# swigert.net
KiCad netlist of a schematic drawn in EAGLE
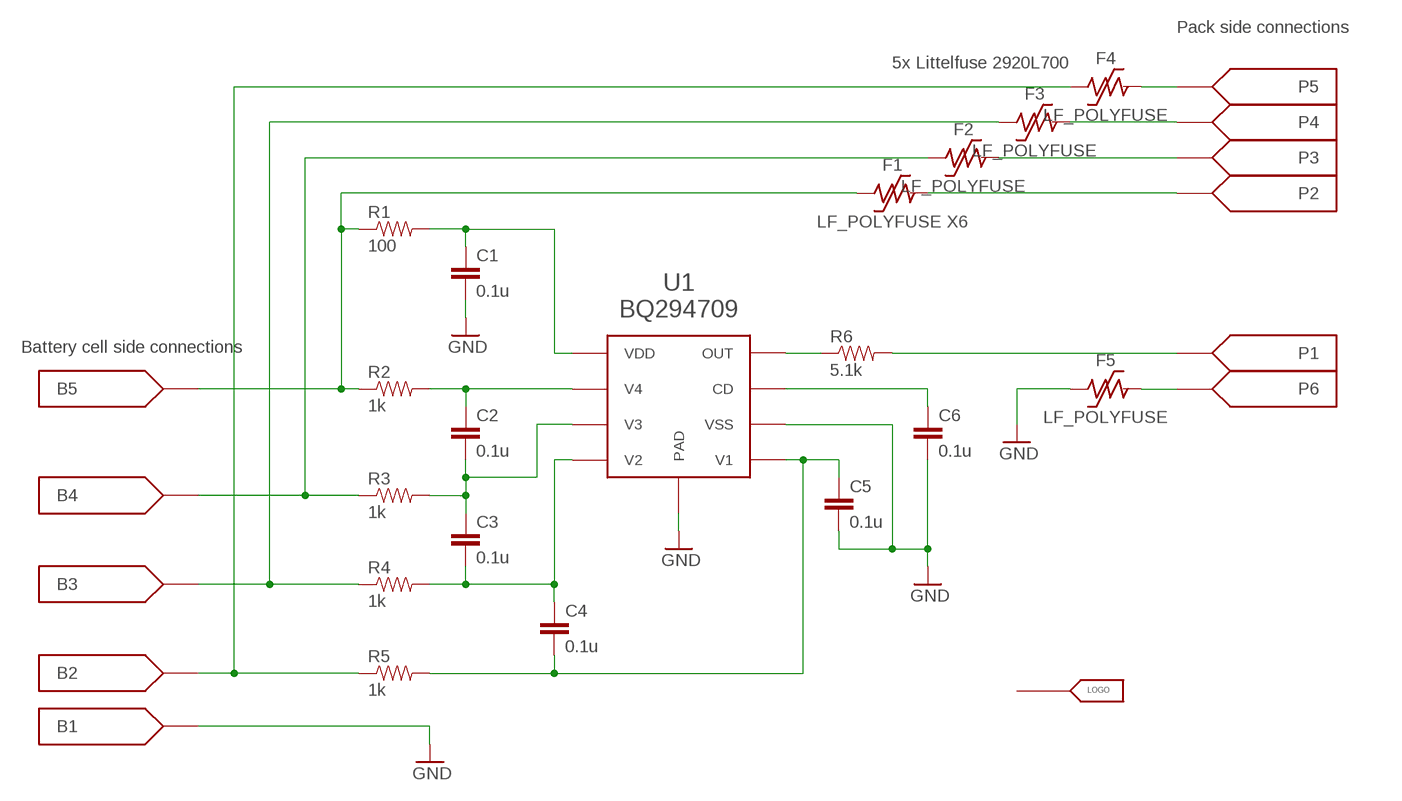
[diagram p0: schematic, sheet 1]

(export (version "E")
  (design (tool "Eeschema 10.0.6"))
  (components
    (comp (ref "B1")
      (value "MOLEX_SRT")
      (footprint "eagle-import:MOLEX_SRT_14-20")
      (libsource (lib "eagle-import") (part "MOLEX_SRT"))
    )
    (comp (ref "B2")
      (value "MOLEX_SRT")
      (footprint "eagle-import:MOLEX_SRT_14-20")
      (libsource (lib "eagle-import") (part "MOLEX_SRT"))
    )
    (comp (ref "B3")
      (value "MOLEX_SRT")
      (footprint "eagle-import:MOLEX_SRT_14-20")
      (libsource (lib "eagle-import") (part "MOLEX_SRT"))
    )
    (comp (ref "B4")
      (value "MOLEX_SRT")
      (footprint "eagle-import:MOLEX_SRT_14-20")
      (libsource (lib "eagle-import") (part "MOLEX_SRT"))
    )
    (comp (ref "B5")
      (value "MOLEX_SRT")
      (footprint "eagle-import:MOLEX_SRT_14-20")
      (libsource (lib "eagle-import") (part "MOLEX_SRT"))
    )
    (comp (ref "C1")
      (value "0.1u")
      (footprint "eagle-import:1206")
      (libsource (lib "eagle-import") (part "CAP1206"))
    )
    (comp (ref "C2")
      (value "0.1u")
      (footprint "eagle-import:1206")
      (libsource (lib "eagle-import") (part "CAP1206"))
    )
    (comp (ref "C3")
      (value "0.1u")
      (footprint "eagle-import:1206")
      (libsource (lib "eagle-import") (part "CAP1206"))
    )
    (comp (ref "C4")
      (value "0.1u")
      (footprint "eagle-import:1206")
      (libsource (lib "eagle-import") (part "CAP1206"))
    )
    (comp (ref "C5")
      (value "0.1u")
      (footprint "eagle-import:1206")
      (libsource (lib "eagle-import") (part "CAP1206"))
    )
    (comp (ref "C6")
      (value "0.1u")
      (footprint "eagle-import:1206")
      (libsource (lib "eagle-import") (part "CAP1206"))
    )
    (comp (ref "F1")
      (value "LF_POLYFUSE X6")
      (footprint "eagle-import:2920")
      (libsource (lib "eagle-import") (part "LF_POLYFUSE"))
    )
    (comp (ref "F2")
      (value "LF_POLYFUSE")
      (footprint "eagle-import:2920")
      (libsource (lib "eagle-import") (part "LF_POLYFUSE"))
    )
    (comp (ref "F3")
      (value "LF_POLYFUSE")
      (footprint "eagle-import:2920")
      (libsource (lib "eagle-import") (part "LF_POLYFUSE"))
    )
    (comp (ref "F4")
      (value "LF_POLYFUSE")
      (footprint "eagle-import:2920")
      (libsource (lib "eagle-import") (part "LF_POLYFUSE"))
    )
    (comp (ref "F5")
      (value "LF_POLYFUSE")
      (footprint "eagle-import:2920")
      (libsource (lib "eagle-import") (part "LF_POLYFUSE"))
    )
    (comp (ref "LOGO")
      (value "SU_LOGO-DUMMY2")
      (footprint "eagle-import:SU_LOGO_SS")
      (libsource (lib "eagle-import") (part "SU_LOGO-DUMMY2"))
    )
    (comp (ref "P1")
      (value "MOLEX_SRT")
      (footprint "eagle-import:MOLEX_SRT_14-20")
      (libsource (lib "eagle-import") (part "MOLEX_SRT"))
    )
    (comp (ref "P2")
      (value "MOLEX_SRT")
      (footprint "eagle-import:MOLEX_SRT_14-20")
      (libsource (lib "eagle-import") (part "MOLEX_SRT"))
    )
    (comp (ref "P3")
      (value "MOLEX_SRT")
      (footprint "eagle-import:MOLEX_SRT_14-20")
      (libsource (lib "eagle-import") (part "MOLEX_SRT"))
    )
    (comp (ref "P4")
      (value "MOLEX_SRT")
      (footprint "eagle-import:MOLEX_SRT_14-20")
      (libsource (lib "eagle-import") (part "MOLEX_SRT"))
    )
    (comp (ref "P5")
      (value "MOLEX_SRT")
      (footprint "eagle-import:MOLEX_SRT_14-20")
      (libsource (lib "eagle-import") (part "MOLEX_SRT"))
    )
    (comp (ref "P6")
      (value "MOLEX_SRT")
      (footprint "eagle-import:MOLEX_SRT_14-20")
      (libsource (lib "eagle-import") (part "MOLEX_SRT"))
    )
    (comp (ref "R1")
      (value "100")
      (footprint "eagle-import:1206")
      (libsource (lib "eagle-import") (part "RESISTOR1206"))
    )
    (comp (ref "R2")
      (value "1k")
      (footprint "eagle-import:1206")
      (libsource (lib "eagle-import") (part "RESISTOR1206"))
    )
    (comp (ref "R3")
      (value "1k")
      (footprint "eagle-import:1206")
      (libsource (lib "eagle-import") (part "RESISTOR1206"))
    )
    (comp (ref "R4")
      (value "1k")
      (footprint "eagle-import:1206")
      (libsource (lib "eagle-import") (part "RESISTOR1206"))
    )
    (comp (ref "R5")
      (value "1k")
      (footprint "eagle-import:1206")
      (libsource (lib "eagle-import") (part "RESISTOR1206"))
    )
    (comp (ref "R6")
      (value "5.1k")
      (footprint "eagle-import:1206")
      (libsource (lib "eagle-import") (part "RESISTOR1206"))
    )
    (comp (ref "U1")
      (value "BQ294709")
      (footprint "eagle-import:WSON8")
      (libsource (lib "eagle-import") (part "BQ2947"))
    )
  )
  (nets
    (net (code "1") (name "GND") (class "Default")
      (node (ref "B1") (pin "P$1") (pinfunction "P1_P$1") (pintype "bidirectional"))
      (node (ref "B1") (pin "P$2") (pinfunction "P1_P$2") (pintype "bidirectional"))
      (node (ref "C1") (pin "2") (pinfunction "2_2") (pintype "passive"))
      (node (ref "C5") (pin "2") (pinfunction "2_2") (pintype "passive"))
      (node (ref "C6") (pin "2") (pinfunction "2_2") (pintype "passive"))
      (node (ref "F5") (pin "P$1") (pinfunction "P$1_P$1") (pintype "bidirectional"))
      (node (ref "U1") (pin "P$6") (pinfunction "VSS_P$6") (pintype "bidirectional"))
      (node (ref "U1") (pin "P$9") (pinfunction "PAD_P$9") (pintype "bidirectional"))
      (node (ref "U1") (pin "P$9_1") (pinfunction "PAD_P$9_1") (pintype "bidirectional"))
      (node (ref "U1") (pin "P$9_2") (pinfunction "PAD_P$9_2") (pintype "bidirectional"))
    )
    (net (code "2") (name "Net-(B2-P1-PadP$1)") (class "Default")
      (node (ref "B2") (pin "P$1") (pinfunction "P1_P$1") (pintype "bidirectional"))
      (node (ref "B2") (pin "P$2") (pinfunction "P1_P$2") (pintype "bidirectional"))
      (node (ref "F4") (pin "P$1") (pinfunction "P$1_P$1") (pintype "bidirectional"))
      (node (ref "R5") (pin "1") (pinfunction "1_1") (pintype "passive"))
    )
    (net (code "3") (name "Net-(B3-P1-PadP$1)") (class "Default")
      (node (ref "B3") (pin "P$1") (pinfunction "P1_P$1") (pintype "bidirectional"))
      (node (ref "B3") (pin "P$2") (pinfunction "P1_P$2") (pintype "bidirectional"))
      (node (ref "F3") (pin "P$1") (pinfunction "P$1_P$1") (pintype "bidirectional"))
      (node (ref "R4") (pin "1") (pinfunction "1_1") (pintype "passive"))
    )
    (net (code "4") (name "Net-(B4-P1-PadP$1)") (class "Default")
      (node (ref "B4") (pin "P$1") (pinfunction "P1_P$1") (pintype "bidirectional"))
      (node (ref "B4") (pin "P$2") (pinfunction "P1_P$2") (pintype "bidirectional"))
      (node (ref "F2") (pin "P$1") (pinfunction "P$1_P$1") (pintype "bidirectional"))
      (node (ref "R3") (pin "1") (pinfunction "1_1") (pintype "passive"))
    )
    (net (code "5") (name "Net-(B5-P1-PadP$1)") (class "Default")
      (node (ref "B5") (pin "P$1") (pinfunction "P1_P$1") (pintype "bidirectional"))
      (node (ref "B5") (pin "P$2") (pinfunction "P1_P$2") (pintype "bidirectional"))
      (node (ref "F1") (pin "P$1") (pinfunction "P$1_P$1") (pintype "bidirectional"))
      (node (ref "R1") (pin "1") (pinfunction "1_1") (pintype "passive"))
      (node (ref "R2") (pin "1") (pinfunction "1_1") (pintype "passive"))
    )
    (net (code "6") (name "Net-(F1-PadP$2)") (class "Default")
      (node (ref "F1") (pin "P$2") (pinfunction "P$2_P$2") (pintype "bidirectional"))
      (node (ref "P2") (pin "P$1") (pinfunction "P1_P$1") (pintype "bidirectional"))
      (node (ref "P2") (pin "P$2") (pinfunction "P1_P$2") (pintype "bidirectional"))
    )
    (net (code "7") (name "Net-(F2-PadP$2)") (class "Default")
      (node (ref "F2") (pin "P$2") (pinfunction "P$2_P$2") (pintype "bidirectional"))
      (node (ref "P3") (pin "P$1") (pinfunction "P1_P$1") (pintype "bidirectional"))
      (node (ref "P3") (pin "P$2") (pinfunction "P1_P$2") (pintype "bidirectional"))
    )
    (net (code "8") (name "Net-(F3-PadP$2)") (class "Default")
      (node (ref "F3") (pin "P$2") (pinfunction "P$2_P$2") (pintype "bidirectional"))
      (node (ref "P4") (pin "P$1") (pinfunction "P1_P$1") (pintype "bidirectional"))
      (node (ref "P4") (pin "P$2") (pinfunction "P1_P$2") (pintype "bidirectional"))
    )
    (net (code "9") (name "Net-(F4-PadP$2)") (class "Default")
      (node (ref "F4") (pin "P$2") (pinfunction "P$2_P$2") (pintype "bidirectional"))
      (node (ref "P5") (pin "P$1") (pinfunction "P1_P$1") (pintype "bidirectional"))
      (node (ref "P5") (pin "P$2") (pinfunction "P1_P$2") (pintype "bidirectional"))
    )
    (net (code "10") (name "Net-(F5-PadP$2)") (class "Default")
      (node (ref "F5") (pin "P$2") (pinfunction "P$2_P$2") (pintype "bidirectional"))
      (node (ref "P6") (pin "P$1") (pinfunction "P1_P$1") (pintype "bidirectional"))
      (node (ref "P6") (pin "P$2") (pinfunction "P1_P$2") (pintype "bidirectional"))
    )
    (net (code "11") (name "Net-(P1-P1-PadP$1)") (class "Default")
      (node (ref "P1") (pin "P$1") (pinfunction "P1_P$1") (pintype "bidirectional"))
      (node (ref "P1") (pin "P$2") (pinfunction "P1_P$2") (pintype "bidirectional"))
      (node (ref "R6") (pin "2") (pinfunction "2_2") (pintype "passive"))
    )
    (net (code "12") (name "Net-(U1-CD)") (class "Default")
      (node (ref "C6") (pin "1") (pinfunction "1_1") (pintype "passive"))
      (node (ref "U1") (pin "P$7") (pinfunction "CD_P$7") (pintype "bidirectional"))
    )
    (net (code "13") (name "Net-(U1-OUT)") (class "Default")
      (node (ref "R6") (pin "1") (pinfunction "1_1") (pintype "passive"))
      (node (ref "U1") (pin "P$8") (pinfunction "OUT_P$8") (pintype "bidirectional"))
    )
    (net (code "14") (name "Net-(U1-V1)") (class "Default")
      (node (ref "C4") (pin "2") (pinfunction "2_2") (pintype "passive"))
      (node (ref "C5") (pin "1") (pinfunction "1_1") (pintype "passive"))
      (node (ref "R5") (pin "2") (pinfunction "2_2") (pintype "passive"))
      (node (ref "U1") (pin "P$5") (pinfunction "V1_P$5") (pintype "bidirectional"))
    )
    (net (code "15") (name "Net-(U1-V2)") (class "Default")
      (node (ref "C3") (pin "2") (pinfunction "2_2") (pintype "passive"))
      (node (ref "C4") (pin "1") (pinfunction "1_1") (pintype "passive"))
      (node (ref "R4") (pin "2") (pinfunction "2_2") (pintype "passive"))
      (node (ref "U1") (pin "P$4") (pinfunction "V2_P$4") (pintype "bidirectional"))
    )
    (net (code "16") (name "Net-(U1-V3)") (class "Default")
      (node (ref "C2") (pin "2") (pinfunction "2_2") (pintype "passive"))
      (node (ref "C3") (pin "1") (pinfunction "1_1") (pintype "passive"))
      (node (ref "R3") (pin "2") (pinfunction "2_2") (pintype "passive"))
      (node (ref "U1") (pin "P$3") (pinfunction "V3_P$3") (pintype "bidirectional"))
    )
    (net (code "17") (name "Net-(U1-V4)") (class "Default")
      (node (ref "C2") (pin "1") (pinfunction "1_1") (pintype "passive"))
      (node (ref "R2") (pin "2") (pinfunction "2_2") (pintype "passive"))
      (node (ref "U1") (pin "P$2") (pinfunction "V4_P$2") (pintype "bidirectional"))
    )
    (net (code "18") (name "Net-(U1-VDD)") (class "Default")
      (node (ref "C1") (pin "1") (pinfunction "1_1") (pintype "passive"))
      (node (ref "R1") (pin "2") (pinfunction "2_2") (pintype "passive"))
      (node (ref "U1") (pin "P$1") (pinfunction "VDD_P$1") (pintype "bidirectional"))
    )
    (net (code "19") (name "unconnected-(LOGO-PadP$1)") (class "Default")
      (node (ref "LOGO") (pin "P$1") (pinfunction "P$1_P$1") (pintype "bidirectional"))
    )
  )
)
